# Kiln_V1.net
KiCad netlist of a schematic drawn in EAGLE
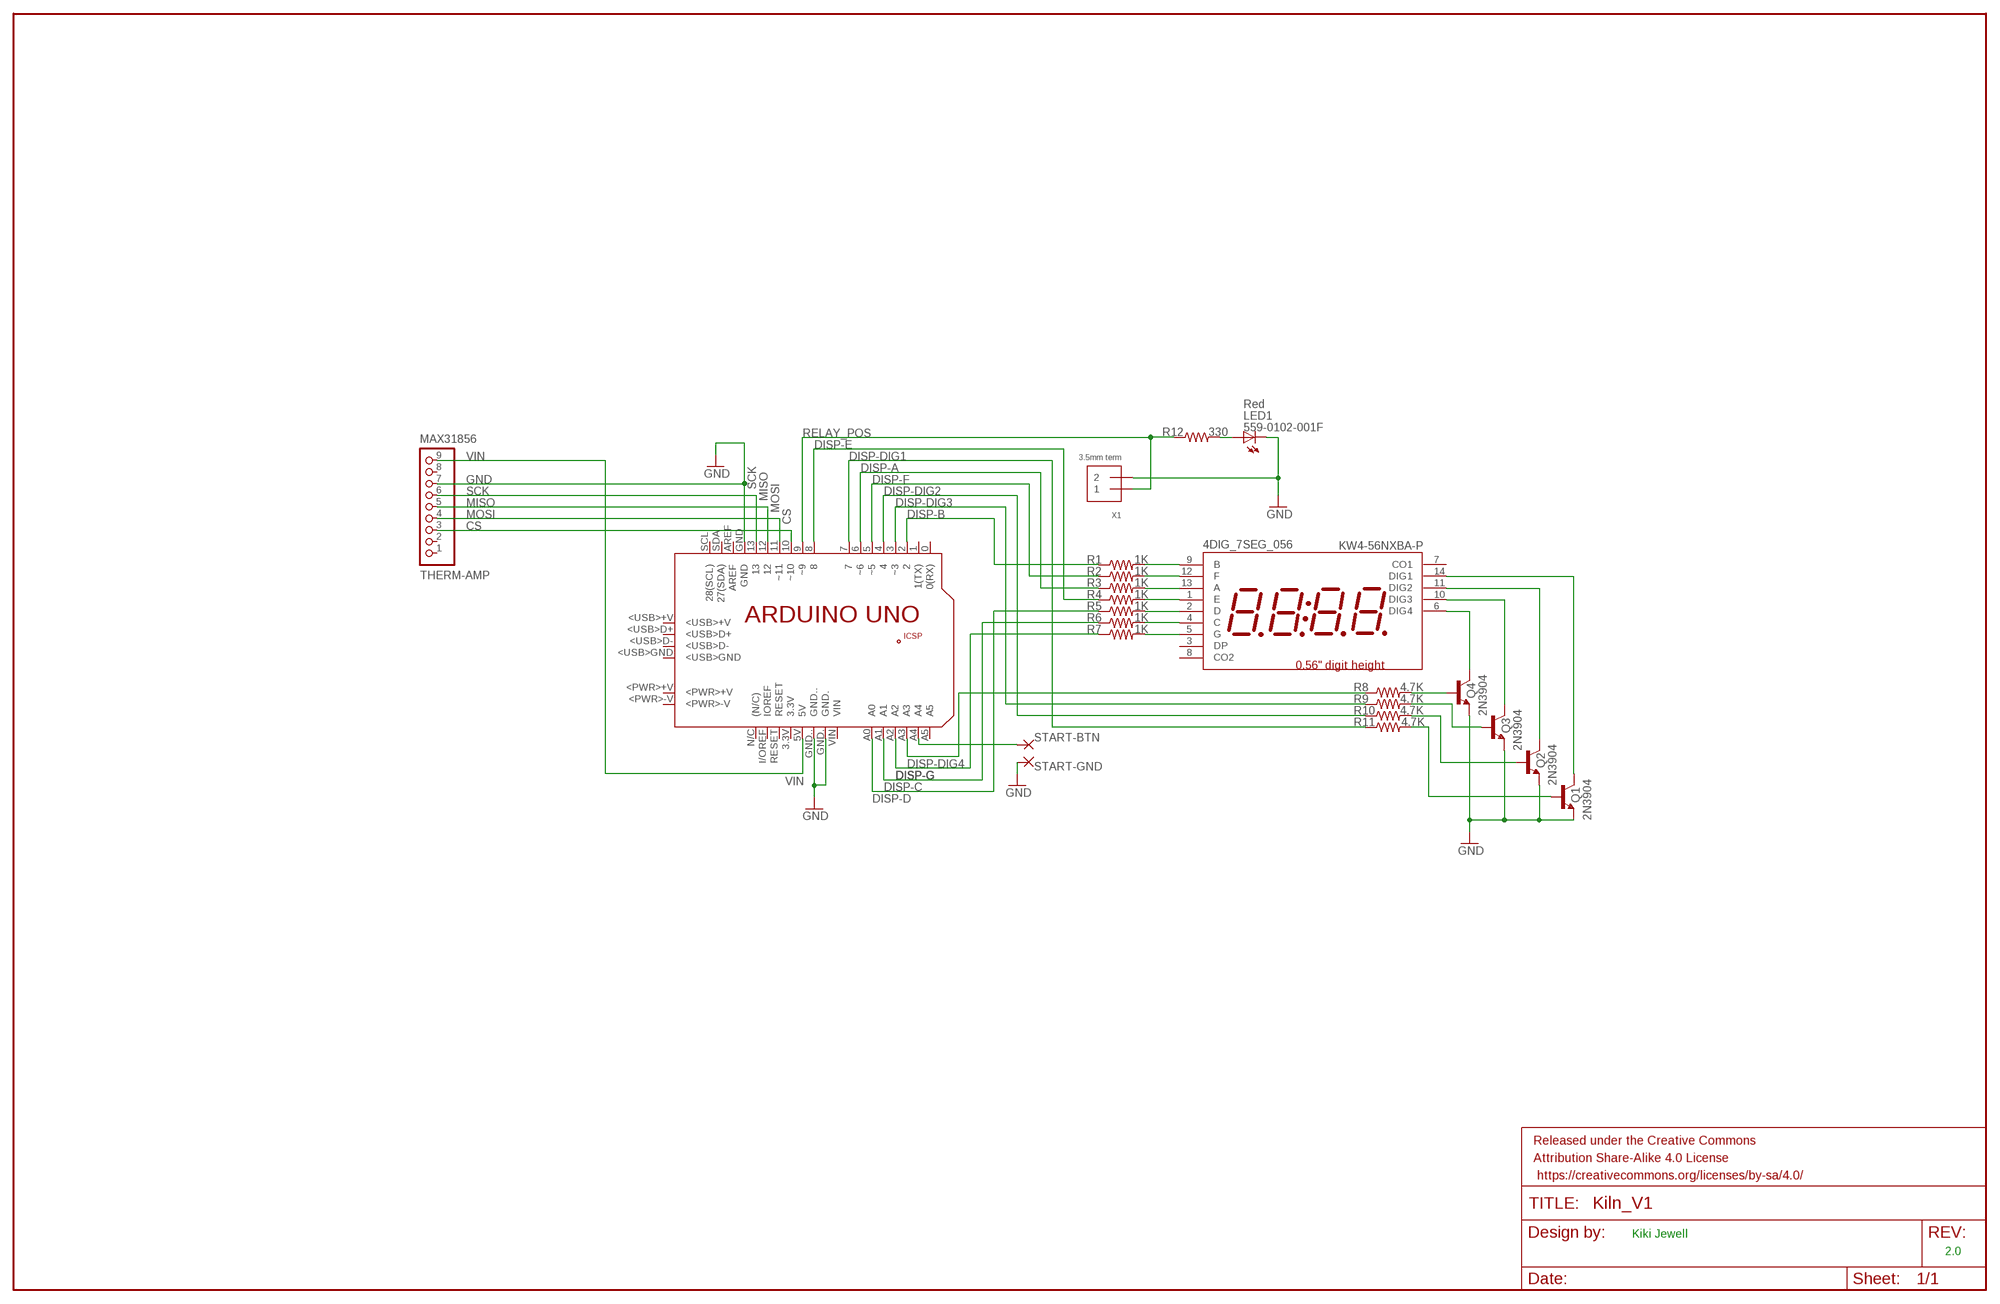
[diagram p0: schematic, sheet 1]

(export (version "E")
  (design (tool "Eeschema 10.0.6"))
  (components
    (comp (ref "4DIG_7SEG_056")
      (value "KW4-56NXBA-P")
      (footprint "eagle-import:4DIG_7SEG_056")
      (libsource (lib "eagle-import") (part "4DIG_7SEG_056"))
    )
    (comp (ref "FRAME1")
      (value "FRAME-LEDGER")
      (footprint "eagle-import:CREATIVE_COMMONS")
      (libsource (lib "eagle-import") (part "FRAME-LEDGER"))
    )
    (comp (ref "LED1")
      (value "559-0102-001F")
      (footprint "eagle-import:LED3MM")
      (fields (field (name "LABEL") "Red"))
      (libsource (lib "eagle-import") (part "LED3MM"))
    )
    (comp (ref "PCB1")
      (value "ARDUINO_UNO")
      (footprint "eagle-import:ARDUINO_UNO")
      (libsource (lib "eagle-import") (part "ARDUINO_UNO"))
    )
    (comp (ref "Q1")
      (value "2N3904")
      (footprint "eagle-import:TO92")
      (libsource (lib "eagle-import") (part "2N3904"))
    )
    (comp (ref "Q2")
      (value "2N3904")
      (footprint "eagle-import:TO92")
      (libsource (lib "eagle-import") (part "2N3904"))
    )
    (comp (ref "Q3")
      (value "2N3904")
      (footprint "eagle-import:TO92")
      (libsource (lib "eagle-import") (part "2N3904"))
    )
    (comp (ref "Q4")
      (value "2N3904")
      (footprint "eagle-import:TO92")
      (libsource (lib "eagle-import") (part "2N3904"))
    )
    (comp (ref "R1")
      (value "1K")
      (footprint "eagle-import:1206")
      (libsource (lib "eagle-import") (part "RESISTOR1206"))
    )
    (comp (ref "R2")
      (value "1K")
      (footprint "eagle-import:1206")
      (libsource (lib "eagle-import") (part "RESISTOR1206"))
    )
    (comp (ref "R3")
      (value "1K")
      (footprint "eagle-import:1206")
      (libsource (lib "eagle-import") (part "RESISTOR1206"))
    )
    (comp (ref "R4")
      (value "1K")
      (footprint "eagle-import:1206")
      (libsource (lib "eagle-import") (part "RESISTOR1206"))
    )
    (comp (ref "R5")
      (value "1K")
      (footprint "eagle-import:1206")
      (libsource (lib "eagle-import") (part "RESISTOR1206"))
    )
    (comp (ref "R6")
      (value "1K")
      (footprint "eagle-import:1206")
      (libsource (lib "eagle-import") (part "RESISTOR1206"))
    )
    (comp (ref "R7")
      (value "1K")
      (footprint "eagle-import:1206")
      (libsource (lib "eagle-import") (part "RESISTOR1206"))
    )
    (comp (ref "R8")
      (value "4.7K")
      (footprint "eagle-import:1206")
      (libsource (lib "eagle-import") (part "RESISTOR1206"))
    )
    (comp (ref "R9")
      (value "4.7K")
      (footprint "eagle-import:1206")
      (libsource (lib "eagle-import") (part "RESISTOR1206"))
    )
    (comp (ref "R10")
      (value "4.7K")
      (footprint "eagle-import:1206")
      (libsource (lib "eagle-import") (part "RESISTOR1206"))
    )
    (comp (ref "R11")
      (value "4.7K")
      (footprint "eagle-import:1206")
      (libsource (lib "eagle-import") (part "RESISTOR1206"))
    )
    (comp (ref "R12")
      (value "330")
      (footprint "eagle-import:1206")
      (libsource (lib "eagle-import") (part "RESISTOR1206"))
    )
    (comp (ref "START-BTN")
      (value "WIREPAD2,54/1,1")
      (footprint "eagle-import:2,54_1,1")
      (libsource (lib "eagle-import") (part "WIREPAD2,54/1,1"))
    )
    (comp (ref "START-GND")
      (value "WIREPAD2,54/1,1")
      (footprint "eagle-import:2,54_1,1")
      (libsource (lib "eagle-import") (part "WIREPAD2,54/1,1"))
    )
    (comp (ref "THERM-AMP")
      (value "MAX31856")
      (footprint "eagle-import:1X09_ROUND_70")
      (libsource (lib "eagle-import") (part "HEADER-1X970MIL"))
    )
    (comp (ref "X1")
      (value "3.5mm term")
      (footprint "eagle-import:TERMBLOCK_1X2-3.5MM")
      (libsource (lib "eagle-import") (part "TERMBLOCK_1X2"))
    )
  )
  (nets
    (net (code "1") (name "/CS") (class "Default")
      (node (ref "PCB1") (pin "10") (pinfunction "~{10}_10") (pintype "bidirectional"))
      (node (ref "THERM-AMP") (pin "3") (pinfunction "3_3") (pintype "passive"))
    )
    (net (code "2") (name "/DISP-A") (class "Default")
      (node (ref "PCB1") (pin "6") (pinfunction "~{6}_6") (pintype "bidirectional"))
      (node (ref "R3") (pin "1") (pinfunction "1_1") (pintype "passive"))
    )
    (net (code "3") (name "/DISP-B") (class "Default")
      (node (ref "PCB1") (pin "2") (pinfunction "2_2") (pintype "bidirectional"))
      (node (ref "R1") (pin "1") (pinfunction "1_1") (pintype "passive"))
    )
    (net (code "4") (name "/DISP-C") (class "Default")
      (node (ref "PCB1") (pin "A1") (pinfunction "A1_A1") (pintype "bidirectional"))
      (node (ref "R6") (pin "1") (pinfunction "1_1") (pintype "passive"))
    )
    (net (code "5") (name "/DISP-D") (class "Default")
      (node (ref "PCB1") (pin "A0") (pinfunction "A0_A0") (pintype "bidirectional"))
      (node (ref "R5") (pin "1") (pinfunction "1_1") (pintype "passive"))
    )
    (net (code "6") (name "/DISP-DIG1") (class "Default")
      (node (ref "PCB1") (pin "7") (pinfunction "7_7") (pintype "bidirectional"))
      (node (ref "R11") (pin "1") (pinfunction "1_1") (pintype "passive"))
    )
    (net (code "7") (name "/DISP-DIG2") (class "Default")
      (node (ref "PCB1") (pin "4") (pinfunction "4_4") (pintype "bidirectional"))
      (node (ref "R10") (pin "1") (pinfunction "1_1") (pintype "passive"))
    )
    (net (code "8") (name "/DISP-DIG3") (class "Default")
      (node (ref "PCB1") (pin "3") (pinfunction "~{3}_3") (pintype "bidirectional"))
      (node (ref "R9") (pin "1") (pinfunction "1_1") (pintype "passive"))
    )
    (net (code "9") (name "/DISP-DIG4") (class "Default")
      (node (ref "PCB1") (pin "A3") (pinfunction "A3_A3") (pintype "bidirectional"))
      (node (ref "R8") (pin "1") (pinfunction "1_1") (pintype "passive"))
    )
    (net (code "10") (name "/DISP-E") (class "Default")
      (node (ref "PCB1") (pin "8") (pinfunction "8_8") (pintype "bidirectional"))
      (node (ref "R4") (pin "1") (pinfunction "1_1") (pintype "passive"))
    )
    (net (code "11") (name "/DISP-F") (class "Default")
      (node (ref "PCB1") (pin "5") (pinfunction "~{5}_5") (pintype "bidirectional"))
      (node (ref "R2") (pin "1") (pinfunction "1_1") (pintype "passive"))
    )
    (net (code "12") (name "/DISP-G") (class "Default")
      (node (ref "PCB1") (pin "A2") (pinfunction "A2_A2") (pintype "bidirectional"))
      (node (ref "R7") (pin "1") (pinfunction "1_1") (pintype "passive"))
    )
    (net (code "13") (name "/MISO") (class "Default")
      (node (ref "PCB1") (pin "12") (pinfunction "12_12") (pintype "bidirectional"))
      (node (ref "THERM-AMP") (pin "5") (pinfunction "5_5") (pintype "passive"))
    )
    (net (code "14") (name "/MOSI") (class "Default")
      (node (ref "PCB1") (pin "11") (pinfunction "~{11}_11") (pintype "bidirectional"))
      (node (ref "THERM-AMP") (pin "4") (pinfunction "4_4") (pintype "passive"))
    )
    (net (code "15") (name "/RELAY_POS") (class "Default")
      (node (ref "PCB1") (pin "9") (pinfunction "~{9}_9") (pintype "bidirectional"))
      (node (ref "R12") (pin "1") (pinfunction "1_1") (pintype "passive"))
      (node (ref "X1") (pin "1") (pinfunction "1_1") (pintype "passive"))
    )
    (net (code "16") (name "/SCK") (class "Default")
      (node (ref "PCB1") (pin "13") (pinfunction "13_13") (pintype "bidirectional"))
      (node (ref "THERM-AMP") (pin "6") (pinfunction "6_6") (pintype "passive"))
    )
    (net (code "17") (name "/VIN") (class "Default")
      (node (ref "PCB1") (pin "5V") (pinfunction "5V_5V") (pintype "bidirectional"))
      (node (ref "THERM-AMP") (pin "9") (pinfunction "9_9") (pintype "passive"))
    )
    (net (code "18") (name "GND") (class "Default")
      (node (ref "LED1") (pin "K") (pinfunction "C_K") (pintype "passive"))
      (node (ref "PCB1") (pin "GND") (pinfunction "GND_GND") (pintype "bidirectional"))
      (node (ref "PCB1") (pin "GND.") (pinfunction "GND._GND.") (pintype "bidirectional"))
      (node (ref "PCB1") (pin "GND..") (pinfunction "GND.._GND..") (pintype "bidirectional"))
      (node (ref "Q1") (pin "3") (pinfunction "E_3") (pintype "passive"))
      (node (ref "Q2") (pin "3") (pinfunction "E_3") (pintype "passive"))
      (node (ref "Q3") (pin "3") (pinfunction "E_3") (pintype "passive"))
      (node (ref "Q4") (pin "3") (pinfunction "E_3") (pintype "passive"))
      (node (ref "START-GND") (pin "1") (pinfunction "P_1") (pintype "passive"))
      (node (ref "THERM-AMP") (pin "7") (pinfunction "7_7") (pintype "passive"))
      (node (ref "X1") (pin "2") (pinfunction "2_2") (pintype "passive"))
    )
    (net (code "19") (name "Net-(4DIG_7SEG_056-A)") (class "Default")
      (node (ref "4DIG_7SEG_056") (pin "13") (pinfunction "A_13") (pintype "bidirectional"))
      (node (ref "R3") (pin "2") (pinfunction "2_2") (pintype "passive"))
    )
    (net (code "20") (name "Net-(4DIG_7SEG_056-B)") (class "Default")
      (node (ref "4DIG_7SEG_056") (pin "9") (pinfunction "B_9") (pintype "bidirectional"))
      (node (ref "R1") (pin "2") (pinfunction "2_2") (pintype "passive"))
    )
    (net (code "21") (name "Net-(4DIG_7SEG_056-C)") (class "Default")
      (node (ref "4DIG_7SEG_056") (pin "4") (pinfunction "C_4") (pintype "bidirectional"))
      (node (ref "R6") (pin "2") (pinfunction "2_2") (pintype "passive"))
    )
    (net (code "22") (name "Net-(4DIG_7SEG_056-D)") (class "Default")
      (node (ref "4DIG_7SEG_056") (pin "2") (pinfunction "D_2") (pintype "bidirectional"))
      (node (ref "R5") (pin "2") (pinfunction "2_2") (pintype "passive"))
    )
    (net (code "23") (name "Net-(4DIG_7SEG_056-DIG1)") (class "Default")
      (node (ref "4DIG_7SEG_056") (pin "14") (pinfunction "DIG1_14") (pintype "bidirectional"))
      (node (ref "Q1") (pin "1") (pinfunction "C_1") (pintype "passive"))
    )
    (net (code "24") (name "Net-(4DIG_7SEG_056-DIG2)") (class "Default")
      (node (ref "4DIG_7SEG_056") (pin "11") (pinfunction "DIG2_11") (pintype "bidirectional"))
      (node (ref "Q2") (pin "1") (pinfunction "C_1") (pintype "passive"))
    )
    (net (code "25") (name "Net-(4DIG_7SEG_056-DIG3)") (class "Default")
      (node (ref "4DIG_7SEG_056") (pin "10") (pinfunction "DIG3_10") (pintype "bidirectional"))
      (node (ref "Q3") (pin "1") (pinfunction "C_1") (pintype "passive"))
    )
    (net (code "26") (name "Net-(4DIG_7SEG_056-DIG4)") (class "Default")
      (node (ref "4DIG_7SEG_056") (pin "6") (pinfunction "DIG4_6") (pintype "bidirectional"))
      (node (ref "Q4") (pin "1") (pinfunction "C_1") (pintype "passive"))
    )
    (net (code "27") (name "Net-(4DIG_7SEG_056-E)") (class "Default")
      (node (ref "4DIG_7SEG_056") (pin "1") (pinfunction "E_1") (pintype "bidirectional"))
      (node (ref "R4") (pin "2") (pinfunction "2_2") (pintype "passive"))
    )
    (net (code "28") (name "Net-(4DIG_7SEG_056-F)") (class "Default")
      (node (ref "4DIG_7SEG_056") (pin "12") (pinfunction "F_12") (pintype "bidirectional"))
      (node (ref "R2") (pin "2") (pinfunction "2_2") (pintype "passive"))
    )
    (net (code "29") (name "Net-(4DIG_7SEG_056-G)") (class "Default")
      (node (ref "4DIG_7SEG_056") (pin "5") (pinfunction "G_5") (pintype "bidirectional"))
      (node (ref "R7") (pin "2") (pinfunction "2_2") (pintype "passive"))
    )
    (net (code "30") (name "Net-(LED1-PadA)") (class "Default")
      (node (ref "LED1") (pin "A") (pinfunction "A_A") (pintype "passive"))
      (node (ref "R12") (pin "2") (pinfunction "2_2") (pintype "passive"))
    )
    (net (code "31") (name "Net-(Q1-B)") (class "Default")
      (node (ref "Q1") (pin "2") (pinfunction "B_2") (pintype "passive"))
      (node (ref "R11") (pin "2") (pinfunction "2_2") (pintype "passive"))
    )
    (net (code "32") (name "Net-(Q2-B)") (class "Default")
      (node (ref "Q2") (pin "2") (pinfunction "B_2") (pintype "passive"))
      (node (ref "R10") (pin "2") (pinfunction "2_2") (pintype "passive"))
    )
    (net (code "33") (name "Net-(Q3-B)") (class "Default")
      (node (ref "Q3") (pin "2") (pinfunction "B_2") (pintype "passive"))
      (node (ref "R9") (pin "2") (pinfunction "2_2") (pintype "passive"))
    )
    (net (code "34") (name "Net-(Q4-B)") (class "Default")
      (node (ref "Q4") (pin "2") (pinfunction "B_2") (pintype "passive"))
      (node (ref "R8") (pin "2") (pinfunction "2_2") (pintype "passive"))
    )
    (net (code "35") (name "Net-(START-BTN-P)") (class "Default")
      (node (ref "PCB1") (pin "A4") (pinfunction "A4_A4") (pintype "bidirectional"))
      (node (ref "START-BTN") (pin "1") (pinfunction "P_1") (pintype "passive"))
    )
    (net (code "36") (name "unconnected-(4DIG_7SEG_056-CO1-Pad7)") (class "Default")
      (node (ref "4DIG_7SEG_056") (pin "7") (pinfunction "CO1_7") (pintype "bidirectional"))
    )
    (net (code "37") (name "unconnected-(4DIG_7SEG_056-CO2-Pad8)") (class "Default")
      (node (ref "4DIG_7SEG_056") (pin "8") (pinfunction "CO2_8") (pintype "bidirectional"))
    )
    (net (code "38") (name "unconnected-(4DIG_7SEG_056-DP-Pad3)") (class "Default")
      (node (ref "4DIG_7SEG_056") (pin "3") (pinfunction "DP_3") (pintype "bidirectional"))
    )
    (net (code "39") (name "unconnected-(PCB1-(N{slash}C)-PadN{slash}C)") (class "Default")
      (node (ref "PCB1") (pin "N/C") (pinfunction "(N/C)_N/C") (pintype "bidirectional"))
    )
    (net (code "40") (name "unconnected-(PCB1-0(RX)-Pad0)") (class "Default")
      (node (ref "PCB1") (pin "0") (pinfunction "0(RX)_0") (pintype "bidirectional"))
    )
    (net (code "41") (name "unconnected-(PCB1-1(TX)-Pad1)") (class "Default")
      (node (ref "PCB1") (pin "1") (pinfunction "1(TX)_1") (pintype "bidirectional"))
    )
    (net (code "42") (name "unconnected-(PCB1-27(SDA)-PadSDA)") (class "Default")
      (node (ref "PCB1") (pin "SDA") (pinfunction "27(SDA)_SDA") (pintype "bidirectional"))
    )
    (net (code "43") (name "unconnected-(PCB1-28(SCL)-PadSCL)") (class "Default")
      (node (ref "PCB1") (pin "SCL") (pinfunction "28(SCL)_SCL") (pintype "bidirectional"))
    )
    (net (code "44") (name "unconnected-(PCB1-IOREF-PadI{slash}OREF)") (class "Default")
      (node (ref "PCB1") (pin "I/OREF") (pinfunction "IOREF_I/OREF") (pintype "bidirectional"))
    )
    (net (code "45") (name "unconnected-(PCB1-Pad+5V)") (class "Default")
      (node (ref "PCB1") (pin "+5V") (pinfunction "+5V_+5V") (pintype "bidirectional"))
    )
    (net (code "46") (name "unconnected-(PCB1-Pad3.3V)") (class "Default")
      (node (ref "PCB1") (pin "3.3V") (pinfunction "3.3V_3.3V") (pintype "bidirectional"))
    )
    (net (code "47") (name "unconnected-(PCB1-Pad<PWR>+V)") (class "Default")
      (node (ref "PCB1") (pin "<PWR>+V") (pinfunction "<PWR>+V_<PWR>+V") (pintype "bidirectional"))
    )
    (net (code "48") (name "unconnected-(PCB1-Pad<PWR>-V)") (class "Default")
      (node (ref "PCB1") (pin "<PWR>-V") (pinfunction "<PWR>-V_<PWR>-V") (pintype "bidirectional"))
    )
    (net (code "49") (name "unconnected-(PCB1-Pad<USB>+V)") (class "Default")
      (node (ref "PCB1") (pin "<USB>+V") (pinfunction "<USB>+V_<USB>+V") (pintype "bidirectional"))
    )
    (net (code "50") (name "unconnected-(PCB1-Pad<USB>D+)") (class "Default")
      (node (ref "PCB1") (pin "<USB>D+") (pinfunction "<USB>D+_<USB>D+") (pintype "bidirectional"))
    )
    (net (code "51") (name "unconnected-(PCB1-Pad<USB>D-)") (class "Default")
      (node (ref "PCB1") (pin "<USB>D-") (pinfunction "<USB>D-_<USB>D-") (pintype "bidirectional"))
    )
    (net (code "52") (name "unconnected-(PCB1-Pad<USB>GND)") (class "Default")
      (node (ref "PCB1") (pin "<USB>GND") (pinfunction "<USB>GND_<USB>GND") (pintype "bidirectional"))
    )
    (net (code "53") (name "unconnected-(PCB1-PadA5)") (class "Default")
      (node (ref "PCB1") (pin "A5") (pinfunction "A5_A5") (pintype "bidirectional"))
    )
    (net (code "54") (name "unconnected-(PCB1-PadAREF)") (class "Default")
      (node (ref "PCB1") (pin "AREF") (pinfunction "AREF_AREF") (pintype "bidirectional"))
    )
    (net (code "55") (name "unconnected-(PCB1-PadGND_)") (class "Default")
      (node (ref "PCB1") (pin "GND_") (pinfunction "GND__GND_") (pintype "bidirectional"))
    )
    (net (code "56") (name "unconnected-(PCB1-PadMISO)") (class "Default")
      (node (ref "PCB1") (pin "MISO") (pinfunction "MISO_MISO") (pintype "bidirectional"))
    )
    (net (code "57") (name "unconnected-(PCB1-PadMOSI)") (class "Default")
      (node (ref "PCB1") (pin "MOSI") (pinfunction "MOSI_MOSI") (pintype "bidirectional"))
    )
    (net (code "58") (name "unconnected-(PCB1-PadRESET)") (class "Default")
      (node (ref "PCB1") (pin "RESET") (pinfunction "RESET_RESET") (pintype "bidirectional"))
    )
    (net (code "59") (name "unconnected-(PCB1-PadRESET.)") (class "Default")
      (node (ref "PCB1") (pin "RESET.") (pinfunction "RESET._RESET.") (pintype "bidirectional"))
    )
    (net (code "60") (name "unconnected-(PCB1-PadSCK)") (class "Default")
      (node (ref "PCB1") (pin "SCK") (pinfunction "SCK_SCK") (pintype "bidirectional"))
    )
    (net (code "61") (name "unconnected-(PCB1-PadVIN)") (class "Default")
      (node (ref "PCB1") (pin "VIN") (pinfunction "VIN_VIN") (pintype "bidirectional"))
    )
    (net (code "62") (name "unconnected-(THERM-AMP-Pad1)") (class "Default")
      (node (ref "THERM-AMP") (pin "1") (pinfunction "1_1") (pintype "passive"))
    )
    (net (code "63") (name "unconnected-(THERM-AMP-Pad2)") (class "Default")
      (node (ref "THERM-AMP") (pin "2") (pinfunction "2_2") (pintype "passive"))
    )
    (net (code "64") (name "unconnected-(THERM-AMP-Pad8)") (class "Default")
      (node (ref "THERM-AMP") (pin "8") (pinfunction "8_8") (pintype "passive"))
    )
  )
)
